# 01-PCIe.net
KiCad netlist of a schematic drawn in Altium Designer
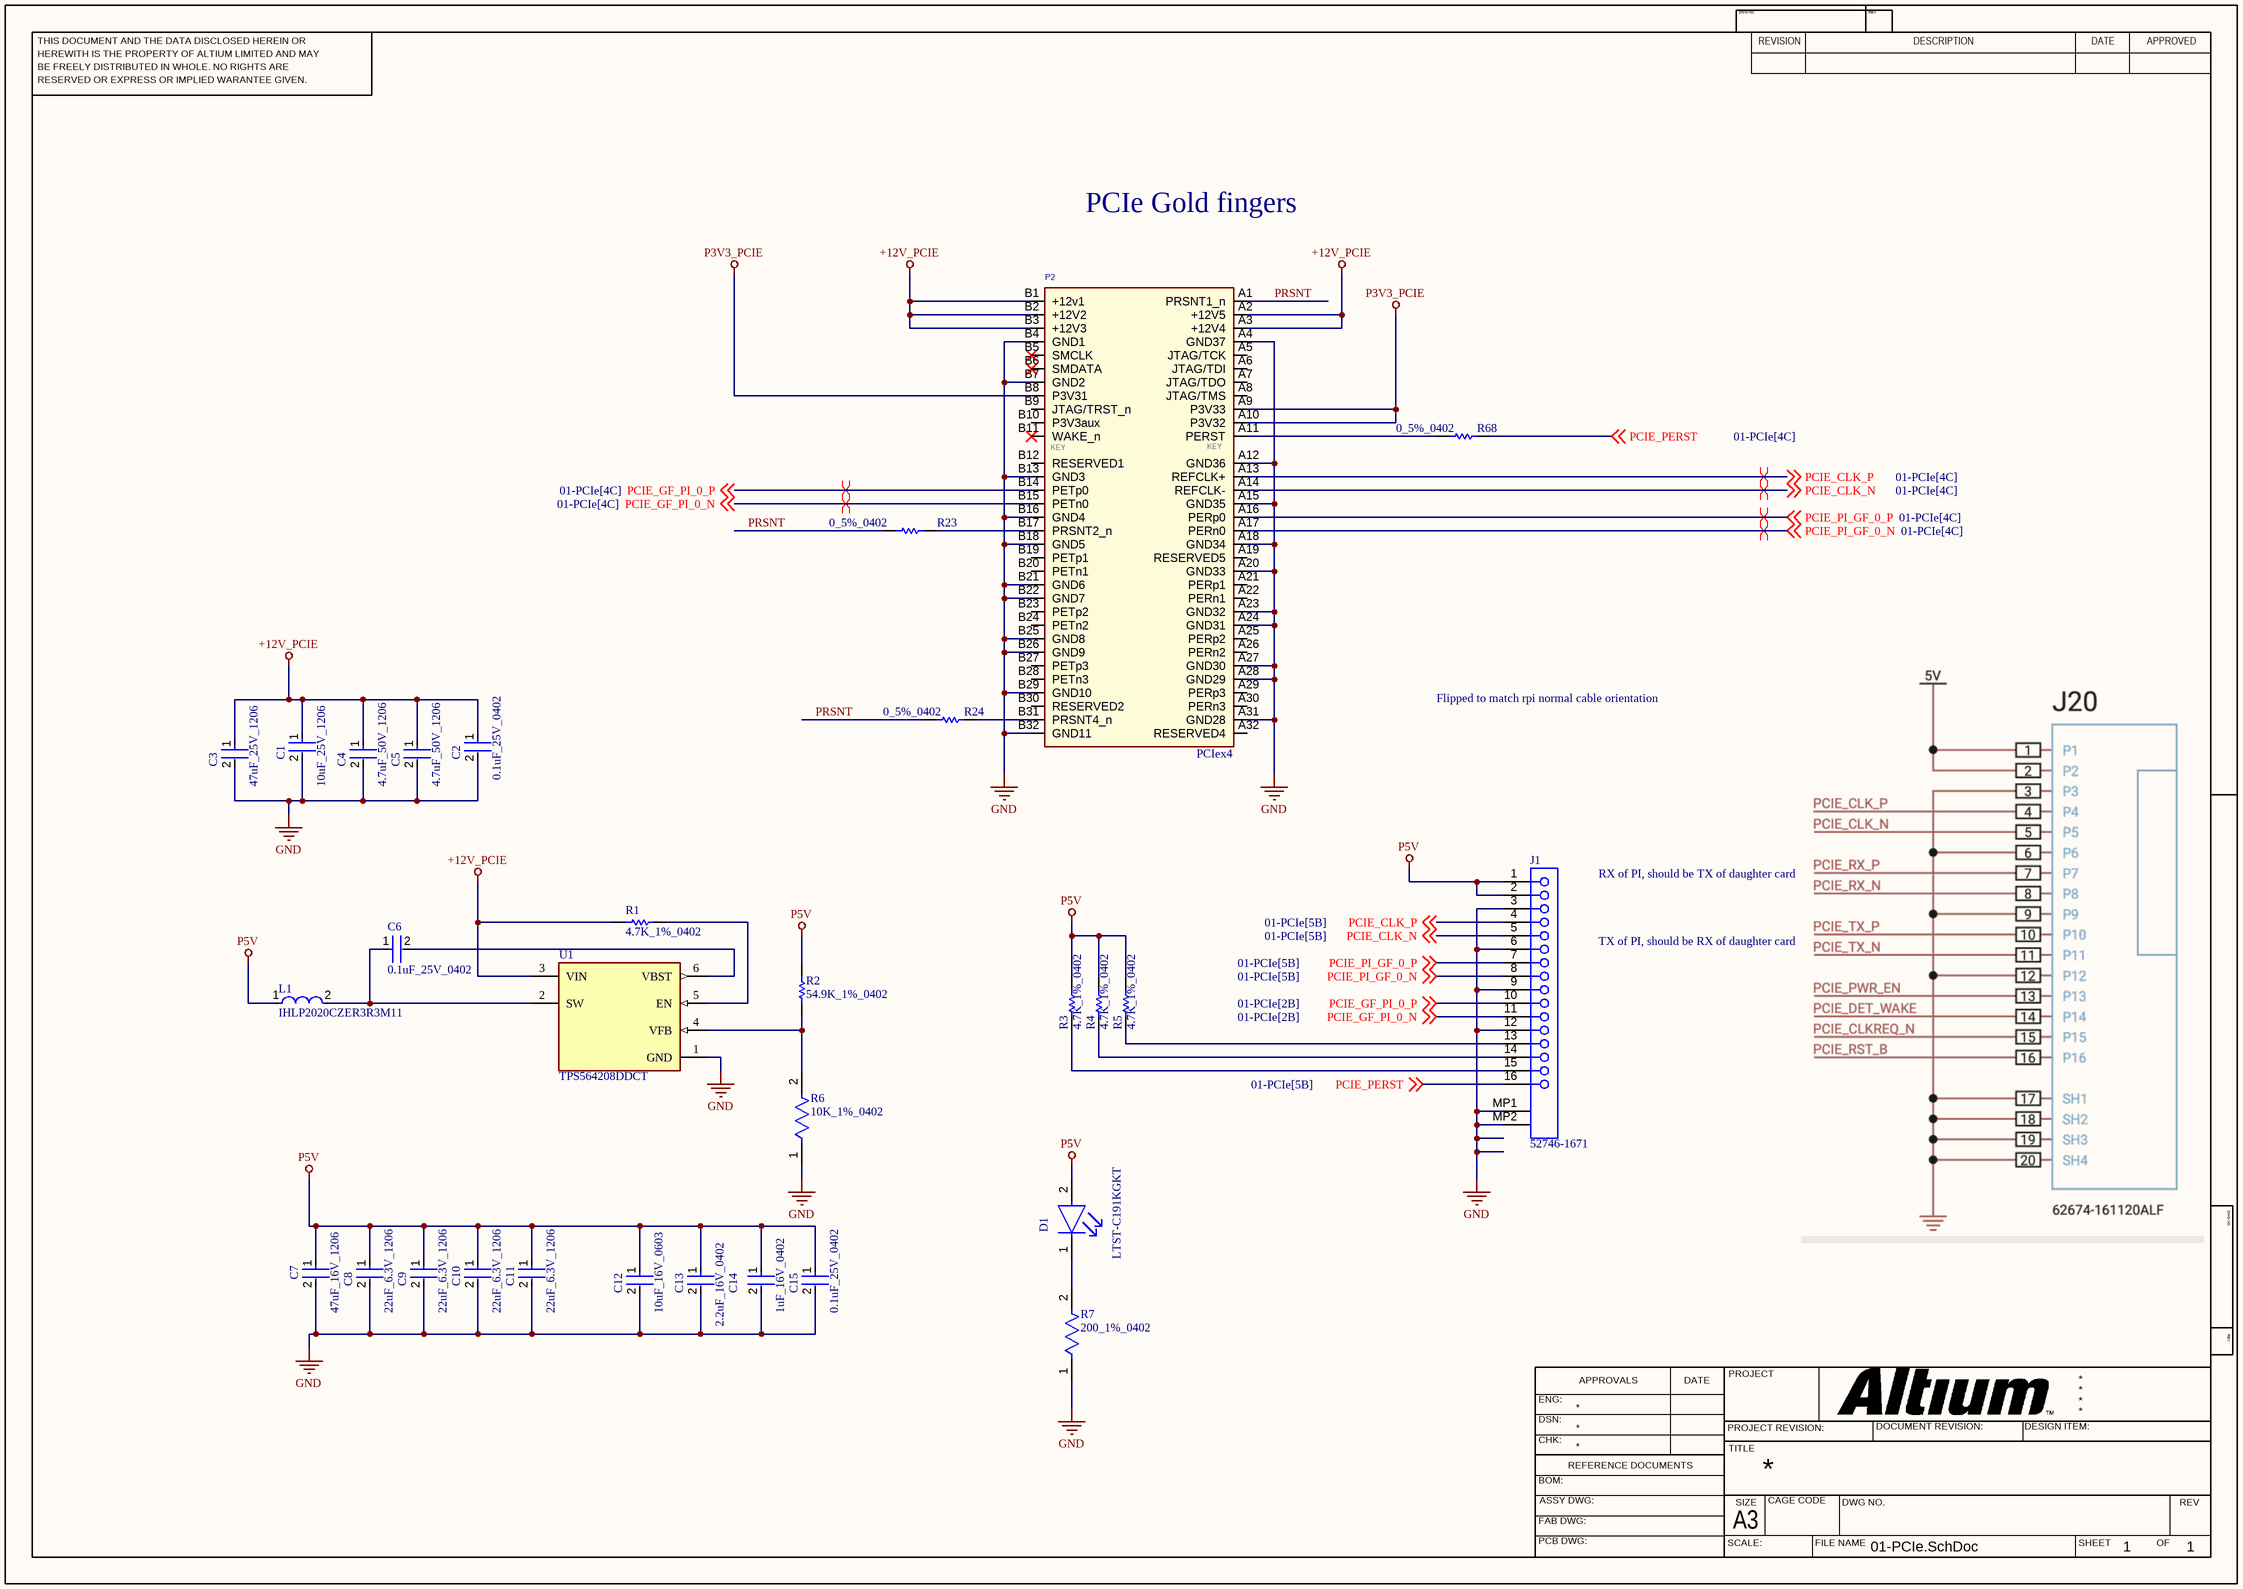
[diagram p0: 01-PCIe.SchDoc]

(export (version "E")
  (design (tool "Eeschema 10.0.6"))
  (components
    (comp (ref "C1")
      (value "10uF_25V_1206")
      (footprint "FP-1206-L_3_2_0_2-W_1_6_0-IPC_A")
      (description "General Purpose Ceramic Capacitor, 1206, 10uF, 20%, X5R, 15%, 25V")
      (fields (field (name "TOLERANCE") "20%"))
      (libsource (lib "Altium Content Vault") (part "02cd4be3c70576c341d710602a673aa"))
    )
    (comp (ref "C2")
      (value "0.1uF_25V_0402")
      (footprint "FP-0402-L_1_0_1-W_0_5_0_1-IPC_C")
      (description "General Purpose Ceramic Capacitor, 0402, 100nF, 10%, X7R, 15%, 25V")
      (fields (field (name "VOLTAGE") "25V") (field (name "TOLERANCE") "10%"))
      (libsource (lib "Altium Content Vault") (part "b4654b650e69147ec39a6b967a45e02"))
    )
    (comp (ref "C3")
      (value "47uF_25V_1206")
      (footprint "FP-C3216-160-0_2-MFG")
      (description "Multilayer Ceramic Capacitors 47uF ±20% 25V X5R SMD 1206")
      (fields (field (name "VOLTAGE") "25V") (field (name "TOLERANCE") "20%"))
      (libsource (lib "Altium Content Vault") (part "11868f565c42a9108669ba33697ecf6"))
    )
    (comp (ref "C4")
      (value "4.7uF_50V_1206")
      (footprint "FP-GRM31C-0_2-e0_3_0_8-IPC_C")
      (description "Chip Multilayer Ceramic Capacitors for General Purpose, 1206, 4.7uF, X7R, 15%, 10%, 50V")
      (fields (field (name "VOLTAGE") "50V") (field (name "TOLERANCE") "10%"))
      (libsource (lib "Altium Content Vault") (part "02cd4be3c70576c341d710602a673aa"))
    )
    (comp (ref "C5")
      (value "4.7uF_50V_1206")
      (footprint "FP-GRM31C-0_2-e0_3_0_8-IPC_C")
      (description "Chip Multilayer Ceramic Capacitors for General Purpose, 1206, 4.7uF, X7R, 15%, 10%, 50V")
      (fields (field (name "VOLTAGE") "50V") (field (name "TOLERANCE") "10%"))
      (libsource (lib "Altium Content Vault") (part "02cd4be3c70576c341d710602a673aa"))
    )
    (comp (ref "C6")
      (value "0.1uF_25V_0402")
      (footprint "FP-0402-L_1_0_1-W_0_5_0_1-IPC_C")
      (description "General Purpose Ceramic Capacitor, 0402, 100nF, 10%, X7R, 15%, 25V")
      (fields (field (name "VOLTAGE") "25V") (field (name "TOLERANCE") "10%"))
      (libsource (lib "Altium Content Vault") (part "b4654b650e69147ec39a6b967a45e02"))
    )
    (comp (ref "C7")
      (value "47uF_16V_1206")
      (footprint "FP-C3216-160-0_2-MFG")
      (description "Multilayer Ceramic Capacitors 47uF ±20% 16V X5R SMD 1206")
      (fields (field (name "TOLERANCE") "20%"))
      (libsource (lib "Altium Content Vault") (part "11868f565c42a9108669ba33697ecf6"))
    )
    (comp (ref "C8")
      (value "22uF_6.3V_1206")
      (footprint "FP-1206-L_3_2_0_2-W_1_6_0-IPC_C")
      (description "General Purpose Ceramic Capacitor, 1206, 22uF, 20%, X5R, 15%, 6.3V")
      (fields (field (name "TOLERANCE") "20%") (field (name "VOLTAGE") "6.3V"))
      (libsource (lib "Altium Content Vault") (part "02cd4be3c70576c341d710602a673aa"))
    )
    (comp (ref "C9")
      (value "22uF_6.3V_1206")
      (footprint "FP-1206-L_3_2_0_2-W_1_6_0-IPC_C")
      (description "General Purpose Ceramic Capacitor, 1206, 22uF, 20%, X5R, 15%, 6.3V")
      (fields (field (name "TOLERANCE") "20%") (field (name "VOLTAGE") "6.3V"))
      (libsource (lib "Altium Content Vault") (part "02cd4be3c70576c341d710602a673aa"))
    )
    (comp (ref "C10")
      (value "22uF_6.3V_1206")
      (footprint "FP-1206-L_3_2_0_2-W_1_6_0-IPC_C")
      (description "General Purpose Ceramic Capacitor, 1206, 22uF, 20%, X5R, 15%, 6.3V")
      (fields (field (name "TOLERANCE") "20%") (field (name "VOLTAGE") "6.3V"))
      (libsource (lib "Altium Content Vault") (part "02cd4be3c70576c341d710602a673aa"))
    )
    (comp (ref "C11")
      (value "22uF_6.3V_1206")
      (footprint "FP-1206-L_3_2_0_2-W_1_6_0-IPC_C")
      (description "General Purpose Ceramic Capacitor, 1206, 22uF, 20%, X5R, 15%, 6.3V")
      (fields (field (name "TOLERANCE") "20%") (field (name "VOLTAGE") "6.3V"))
      (libsource (lib "Altium Content Vault") (part "02cd4be3c70576c341d710602a673aa"))
    )
    (comp (ref "C12")
      (value "10uF_16V_0603")
      (footprint "FP-0603-L_1_6_0_2-W_0_8_0-MFG")
      (description "Multilayer Ceramic Capacitor 10uF 16V X5R 20% SMD 0603 T/R")
      (fields (field (name "TOLERANCE") "20%"))
      (libsource (lib "Altium Content Vault") (part "b4654b650e69147ec39a6b967a45e02"))
    )
    (comp (ref "C13")
      (value "2.2uF_16V_0402")
      (footprint "FP-C1005-050-0_05-IPC_A")
      (description "Multilayer Ceramic Capacitors 2.2μF ±10% 16V X5R SMD 0402")
      (fields (field (name "TOLERANCE") "10%"))
      (libsource (lib "Altium Content Vault") (part "b4654b650e69147ec39a6b967a45e02"))
    )
    (comp (ref "C14")
      (value "1uF_16V_0402")
      (footprint "FP-0402-L_1_0_0_05-W_0_5-IPC_A")
      (description "None")
      (fields (field (name "TOLERANCE") "10%"))
      (libsource (lib "Altium Content Vault") (part "b4654b650e69147ec39a6b967a45e02"))
    )
    (comp (ref "C15")
      (value "0.1uF_25V_0402")
      (footprint "FP-0402-L_1_0_1-W_0_5_0_1-IPC_C")
      (description "General Purpose Ceramic Capacitor, 0402, 100nF, 10%, X7R, 15%, 25V")
      (fields (field (name "VOLTAGE") "25V") (field (name "TOLERANCE") "10%"))
      (libsource (lib "Altium Content Vault") (part "b4654b650e69147ec39a6b967a45e02"))
    )
    (comp (ref "D1")
      (value "LTST-C191KGKT")
      (footprint "FP-LTST-C191KGKT-MFG")
      (description "LED GREEN CLEAR SMD")
      (libsource (lib "Altium Content Vault") (part "8706943c75ba83719d021d2fdc84c58"))
    )
    (comp (ref "J1")
      (value "52746-1671")
      (footprint "MOLX-52746-1671")
      (fields (field (name "MANUFACTURER") "Molex"))
      (libsource (lib "Altium Content Vault") (part "MOLX-52746-1671"))
    )
    (comp (ref "L1")
      (value "IHLP2020CZER3R3M11")
      (footprint "FP-IHLP-2020CZ-FP_1_905x2-MFG")
      (description "Fixed Inductors Commercial Low DCR Series 3.3uH 5.5A 40.4mΩ 20%")
      (fields (field (name "TOLERANCE") "20%"))
      (libsource (lib "Altium Content Vault") (part "725321dda6339637d4d059423bc1c3c"))
    )
    (comp (ref "P2")
      (value "PCIex4")
      (footprint "PCIE_4LANE_EDGE")
      (description "PCIE x4 Edge Connector,OrCAD Symbol,NC")
      (fields (field (name "PART NUMBER") "451") (field (name "MANUFACTURER") "NA"))
      (libsource (lib "Connectors") (part "PCIex4"))
    )
    (comp (ref "R1")
      (value "4.7K_1%_0402")
      (footprint "RESC1005X40X25NL10T10")
      (fields (field (name "MANUFACTURER") "Bourns") (field (name "PART NUMBER") "CR0402-FX-4701GLF"))
      (libsource (lib "Altium Content Vault") (part "RES"))
    )
    (comp (ref "R2")
      (value "54.9K_1%_0402")
      (footprint "RESC1005X40X25ML05T05")
      (fields (field (name "MANUFACTURER") "Panasonic") (field (name "PART NUMBER") "ERJ-2RKF5492X"))
      (libsource (lib "Altium Content Vault") (part "RES"))
    )
    (comp (ref "R3")
      (value "4.7K_1%_0402")
      (footprint "RESC1005X40X25NL10T10")
      (fields (field (name "MANUFACTURER") "Bourns") (field (name "PART NUMBER") "CR0402-FX-4701GLF"))
      (libsource (lib "Altium Content Vault") (part "RES"))
    )
    (comp (ref "R4")
      (value "4.7K_1%_0402")
      (footprint "RESC1005X40X25NL10T10")
      (fields (field (name "MANUFACTURER") "Bourns") (field (name "PART NUMBER") "CR0402-FX-4701GLF"))
      (libsource (lib "Altium Content Vault") (part "RES"))
    )
    (comp (ref "R5")
      (value "4.7K_1%_0402")
      (footprint "RESC1005X40X25NL10T10")
      (fields (field (name "MANUFACTURER") "Bourns") (field (name "PART NUMBER") "CR0402-FX-4701GLF"))
      (libsource (lib "Altium Content Vault") (part "RES"))
    )
    (comp (ref "R6")
      (value "10K_1%_0402")
      (footprint "FP-ERJU02-IPC_A")
      (description "RES 10K OHM 1% 1/10W 0402 SMD")
      (fields (field (name "TOLERANCE") "1%"))
      (libsource (lib "Altium Content Vault") (part "1029c3af85768c4190bb7ad29bc67b5"))
    )
    (comp (ref "R7")
      (value "200_1%_0402")
      (footprint "FP-ERJ2RK-IPC_A")
      (description "RES SMD 200 OHM 1% 1/10W 0402")
      (fields (field (name "TOLERANCE") "1%"))
      (libsource (lib "Altium Content Vault") (part "1029c3af85768c4190bb7ad29bc67b5"))
    )
    (comp (ref "R23")
      (value "0_5%_0402")
      (footprint "RESC1005X40X25LL10T10")
      (fields (field (name "MANUFACTURER") "KOA Speer") (field (name "PART NUMBER") "RK73Z1ETTP"))
      (libsource (lib "Altium Content Vault") (part "RES"))
    )
    (comp (ref "R24")
      (value "0_5%_0402")
      (footprint "RESC1005X40X25LL10T10")
      (fields (field (name "MANUFACTURER") "KOA Speer") (field (name "PART NUMBER") "RK73Z1ETTP"))
      (libsource (lib "Altium Content Vault") (part "RES"))
    )
    (comp (ref "R68")
      (value "0_5%_0402")
      (footprint "RESC1005X40X25LL10T10")
      (fields (field (name "MANUFACTURER") "KOA Speer") (field (name "PART NUMBER") "RK73Z1ETTP"))
      (libsource (lib "Altium Content Vault") (part "RES"))
    )
    (comp (ref "U1")
      (value "TPS564208DDCT")
      (footprint "FP-DDC0006A-IPC_C")
      (description "IC REG BUCK ADJ 4A TSOT23-6")
      (libsource (lib "Altium Content Vault") (part "38226ecfcda63a3f61967f0d2bdf495"))
    )
  )
  (nets
    (net (code "1") (name "+12V_PCIE") (class "Default")
      (node (ref "C1") (pin "1") (pinfunction "1_1") (pintype "passive"))
      (node (ref "C2") (pin "1") (pinfunction "1_1") (pintype "passive"))
      (node (ref "C3") (pin "1") (pinfunction "1_1") (pintype "passive"))
      (node (ref "C4") (pin "1") (pinfunction "1_1") (pintype "passive"))
      (node (ref "C5") (pin "1") (pinfunction "1_1") (pintype "passive"))
      (node (ref "P2") (pin "A2") (pinfunction "+12V5_A2") (pintype "passive"))
      (node (ref "P2") (pin "A3") (pinfunction "+12V4_A3") (pintype "passive"))
      (node (ref "P2") (pin "B1") (pinfunction "+12v1_B1") (pintype "power_in"))
      (node (ref "P2") (pin "B2") (pinfunction "+12V2_B2") (pintype "power_in"))
      (node (ref "P2") (pin "B3") (pinfunction "+12V3_B3") (pintype "power_in"))
      (node (ref "R1") (pin "2") (pinfunction "2_2") (pintype "passive"))
      (node (ref "U1") (pin "3") (pinfunction "VIN_3") (pintype "power_in"))
    )
    (net (code "2") (name "/PRSNT") (class "Default")
      (node (ref "P2") (pin "A1") (pinfunction "PRSNT1_n_A1") (pintype "passive"))
      (node (ref "R23") (pin "1") (pinfunction "1_1") (pintype "passive"))
      (node (ref "R24") (pin "1") (pinfunction "1_1") (pintype "passive"))
    )
    (net (code "3") (name "GND") (class "Default")
      (node (ref "C1") (pin "2") (pinfunction "2_2") (pintype "passive"))
      (node (ref "C10") (pin "2") (pinfunction "2_2") (pintype "passive"))
      (node (ref "C11") (pin "2") (pinfunction "2_2") (pintype "passive"))
      (node (ref "C12") (pin "2") (pinfunction "2_2") (pintype "passive"))
      (node (ref "C13") (pin "2") (pinfunction "2_2") (pintype "passive"))
      (node (ref "C14") (pin "2") (pinfunction "2_2") (pintype "passive"))
      (node (ref "C15") (pin "2") (pinfunction "2_2") (pintype "passive"))
      (node (ref "C2") (pin "2") (pinfunction "2_2") (pintype "passive"))
      (node (ref "C3") (pin "2") (pinfunction "2_2") (pintype "passive"))
      (node (ref "C4") (pin "2") (pinfunction "2_2") (pintype "passive"))
      (node (ref "C5") (pin "2") (pinfunction "2_2") (pintype "passive"))
      (node (ref "C7") (pin "2") (pinfunction "2_2") (pintype "passive"))
      (node (ref "C8") (pin "2") (pinfunction "2_2") (pintype "passive"))
      (node (ref "C9") (pin "2") (pinfunction "2_2") (pintype "passive"))
      (node (ref "J1") (pin "12") (pinfunction "12_12") (pintype "passive"))
      (node (ref "J1") (pin "3") (pinfunction "3_3") (pintype "passive"))
      (node (ref "J1") (pin "6") (pinfunction "6_6") (pintype "passive"))
      (node (ref "J1") (pin "9") (pinfunction "9_9") (pintype "passive"))
      (node (ref "J1") (pin "MP1") (pinfunction "MP1_MP1") (pintype "passive"))
      (node (ref "J1") (pin "MP2") (pinfunction "MP2_MP2") (pintype "passive"))
      (node (ref "P2") (pin "A12") (pinfunction "GND36_A12") (pintype "power_in"))
      (node (ref "P2") (pin "A15") (pinfunction "GND35_A15") (pintype "power_in"))
      (node (ref "P2") (pin "A18") (pinfunction "GND34_A18") (pintype "power_in"))
      (node (ref "P2") (pin "A20") (pinfunction "GND33_A20") (pintype "power_in"))
      (node (ref "P2") (pin "A23") (pinfunction "GND32_A23") (pintype "power_in"))
      (node (ref "P2") (pin "A24") (pinfunction "GND31_A24") (pintype "power_in"))
      (node (ref "P2") (pin "A27") (pinfunction "GND30_A27") (pintype "power_in"))
      (node (ref "P2") (pin "A28") (pinfunction "GND29_A28") (pintype "power_in"))
      (node (ref "P2") (pin "A31") (pinfunction "GND28_A31") (pintype "power_in"))
      (node (ref "P2") (pin "A4") (pinfunction "GND37_A4") (pintype "power_in"))
      (node (ref "P2") (pin "B13") (pinfunction "GND3_B13") (pintype "power_in"))
      (node (ref "P2") (pin "B16") (pinfunction "GND4_B16") (pintype "power_in"))
      (node (ref "P2") (pin "B18") (pinfunction "GND5_B18") (pintype "power_in"))
      (node (ref "P2") (pin "B21") (pinfunction "GND6_B21") (pintype "power_in"))
      (node (ref "P2") (pin "B22") (pinfunction "GND7_B22") (pintype "power_in"))
      (node (ref "P2") (pin "B25") (pinfunction "GND8_B25") (pintype "power_in"))
      (node (ref "P2") (pin "B26") (pinfunction "GND9_B26") (pintype "power_in"))
      (node (ref "P2") (pin "B29") (pinfunction "GND10_B29") (pintype "power_in"))
      (node (ref "P2") (pin "B32") (pinfunction "GND11_B32") (pintype "power_in"))
      (node (ref "P2") (pin "B4") (pinfunction "GND1_B4") (pintype "power_in"))
      (node (ref "P2") (pin "B7") (pinfunction "GND2_B7") (pintype "power_in"))
      (node (ref "R6") (pin "1") (pinfunction "1_1") (pintype "passive"))
      (node (ref "R7") (pin "1") (pinfunction "1_1") (pintype "passive"))
      (node (ref "U1") (pin "1") (pinfunction "GND_1") (pintype "power_in"))
    )
    (net (code "4") (name "Net-(D1-C)") (class "Default")
      (node (ref "D1") (pin "1") (pinfunction "C_1") (pintype "passive"))
      (node (ref "R7") (pin "2") (pinfunction "2_2") (pintype "passive"))
    )
    (net (code "5") (name "Net-(J1-Pad13)") (class "Default")
      (node (ref "J1") (pin "13") (pinfunction "13_13") (pintype "passive"))
      (node (ref "R5") (pin "1") (pinfunction "1_1") (pintype "passive"))
    )
    (net (code "6") (name "Net-(J1-Pad14)") (class "Default")
      (node (ref "J1") (pin "14") (pinfunction "14_14") (pintype "passive"))
      (node (ref "R4") (pin "1") (pinfunction "1_1") (pintype "passive"))
    )
    (net (code "7") (name "Net-(J1-Pad15)") (class "Default")
      (node (ref "J1") (pin "15") (pinfunction "15_15") (pintype "passive"))
      (node (ref "R3") (pin "1") (pinfunction "1_1") (pintype "passive"))
    )
    (net (code "8") (name "Net-(P2-PERST)") (class "Default")
      (node (ref "P2") (pin "A11") (pinfunction "PERST_A11") (pintype "passive"))
      (node (ref "R68") (pin "1") (pinfunction "1_1") (pintype "passive"))
    )
    (net (code "9") (name "Net-(P2-PRSNT2_n)") (class "Default")
      (node (ref "P2") (pin "B17") (pinfunction "PRSNT2_n_B17") (pintype "passive"))
      (node (ref "R23") (pin "2") (pinfunction "2_2") (pintype "passive"))
    )
    (net (code "10") (name "Net-(P2-PRSNT4_n)") (class "Default")
      (node (ref "P2") (pin "B31") (pinfunction "PRSNT4_n_B31") (pintype "passive"))
      (node (ref "R24") (pin "2") (pinfunction "2_2") (pintype "passive"))
    )
    (net (code "11") (name "Net-(U1-EN)") (class "Default")
      (node (ref "R1") (pin "1") (pinfunction "1_1") (pintype "passive"))
      (node (ref "U1") (pin "5") (pinfunction "EN_5") (pintype "input"))
    )
    (net (code "12") (name "Net-(U1-SW)") (class "Default")
      (node (ref "C6") (pin "1") (pinfunction "1_1") (pintype "passive"))
      (node (ref "L1") (pin "2") (pinfunction "2_2") (pintype "passive"))
      (node (ref "U1") (pin "2") (pinfunction "SW_2") (pintype "passive"))
    )
    (net (code "13") (name "Net-(U1-VBST)") (class "Default")
      (node (ref "C6") (pin "2") (pinfunction "2_2") (pintype "passive"))
      (node (ref "U1") (pin "6") (pinfunction "VBST_6") (pintype "output"))
    )
    (net (code "14") (name "Net-(U1-VFB)") (class "Default")
      (node (ref "R2") (pin "1") (pinfunction "1_1") (pintype "passive"))
      (node (ref "R6") (pin "2") (pinfunction "2_2") (pintype "passive"))
      (node (ref "U1") (pin "4") (pinfunction "VFB_4") (pintype "input"))
    )
    (net (code "15") (name "P3V3_PCIE") (class "Default")
      (node (ref "P2") (pin "A10") (pinfunction "P3V32_A10") (pintype "passive"))
      (node (ref "P2") (pin "A9") (pinfunction "P3V33_A9") (pintype "passive"))
      (node (ref "P2") (pin "B8") (pinfunction "P3V31_B8") (pintype "power_in"))
    )
    (net (code "16") (name "P5V") (class "Default")
      (node (ref "C10") (pin "1") (pinfunction "1_1") (pintype "passive"))
      (node (ref "C11") (pin "1") (pinfunction "1_1") (pintype "passive"))
      (node (ref "C12") (pin "1") (pinfunction "1_1") (pintype "passive"))
      (node (ref "C13") (pin "1") (pinfunction "1_1") (pintype "passive"))
      (node (ref "C14") (pin "1") (pinfunction "1_1") (pintype "passive"))
      (node (ref "C15") (pin "1") (pinfunction "1_1") (pintype "passive"))
      (node (ref "C7") (pin "1") (pinfunction "1_1") (pintype "passive"))
      (node (ref "C8") (pin "1") (pinfunction "1_1") (pintype "passive"))
      (node (ref "C9") (pin "1") (pinfunction "1_1") (pintype "passive"))
      (node (ref "D1") (pin "2") (pinfunction "A_2") (pintype "passive"))
      (node (ref "J1") (pin "1") (pinfunction "1_1") (pintype "passive"))
      (node (ref "J1") (pin "2") (pinfunction "2_2") (pintype "passive"))
      (node (ref "L1") (pin "1") (pinfunction "1_1") (pintype "passive"))
      (node (ref "R2") (pin "2") (pinfunction "2_2") (pintype "passive"))
      (node (ref "R3") (pin "2") (pinfunction "2_2") (pintype "passive"))
      (node (ref "R4") (pin "2") (pinfunction "2_2") (pintype "passive"))
      (node (ref "R5") (pin "2") (pinfunction "2_2") (pintype "passive"))
    )
    (net (code "17") (name "PCIE_CLK_N") (class "Default")
      (node (ref "J1") (pin "5") (pinfunction "5_5") (pintype "passive"))
      (node (ref "P2") (pin "A14") (pinfunction "REFCLK-_A14") (pintype "passive"))
    )
    (net (code "18") (name "PCIE_CLK_P") (class "Default")
      (node (ref "J1") (pin "4") (pinfunction "4_4") (pintype "passive"))
      (node (ref "P2") (pin "A13") (pinfunction "REFCLK+_A13") (pintype "passive"))
    )
    (net (code "19") (name "PCIE_GF_PI_0_N") (class "Default")
      (node (ref "J1") (pin "11") (pinfunction "11_11") (pintype "passive"))
      (node (ref "P2") (pin "B15") (pinfunction "PETn0_B15") (pintype "passive"))
    )
    (net (code "20") (name "PCIE_GF_PI_0_P") (class "Default")
      (node (ref "J1") (pin "10") (pinfunction "10_10") (pintype "passive"))
      (node (ref "P2") (pin "B14") (pinfunction "PETp0_B14") (pintype "passive"))
    )
    (net (code "21") (name "PCIE_PERST") (class "Default")
      (node (ref "J1") (pin "16") (pinfunction "16_16") (pintype "passive"))
      (node (ref "R68") (pin "2") (pinfunction "2_2") (pintype "passive"))
    )
    (net (code "22") (name "PCIE_PI_GF_0_N") (class "Default")
      (node (ref "J1") (pin "8") (pinfunction "8_8") (pintype "passive"))
      (node (ref "P2") (pin "A17") (pinfunction "PERn0_A17") (pintype "passive"))
    )
    (net (code "23") (name "PCIE_PI_GF_0_P") (class "Default")
      (node (ref "J1") (pin "7") (pinfunction "7_7") (pintype "passive"))
      (node (ref "P2") (pin "A16") (pinfunction "PERp0_A16") (pintype "passive"))
    )
    (net (code "24") (name "unconnected-(P2-JTAG{slash}TCK-PadA5)") (class "Default")
      (node (ref "P2") (pin "A5") (pinfunction "JTAG/TCK_A5") (pintype "passive"))
    )
    (net (code "25") (name "unconnected-(P2-JTAG{slash}TDI-PadA6)") (class "Default")
      (node (ref "P2") (pin "A6") (pinfunction "JTAG/TDI_A6") (pintype "passive"))
    )
    (net (code "26") (name "unconnected-(P2-JTAG{slash}TDO-PadA7)") (class "Default")
      (node (ref "P2") (pin "A7") (pinfunction "JTAG/TDO_A7") (pintype "passive"))
    )
    (net (code "27") (name "unconnected-(P2-JTAG{slash}TMS-PadA8)") (class "Default")
      (node (ref "P2") (pin "A8") (pinfunction "JTAG/TMS_A8") (pintype "passive"))
    )
    (net (code "28") (name "unconnected-(P2-JTAG{slash}TRST_n-PadB9)") (class "Default")
      (node (ref "P2") (pin "B9") (pinfunction "JTAG/TRST_n_B9") (pintype "passive"))
    )
    (net (code "29") (name "unconnected-(P2-P3V3aux-PadB10)") (class "Default")
      (node (ref "P2") (pin "B10") (pinfunction "P3V3aux_B10") (pintype "passive"))
    )
    (net (code "30") (name "unconnected-(P2-PERn1-PadA22)") (class "Default")
      (node (ref "P2") (pin "A22") (pinfunction "PERn1_A22") (pintype "passive"))
    )
    (net (code "31") (name "unconnected-(P2-PERn2-PadA26)") (class "Default")
      (node (ref "P2") (pin "A26") (pinfunction "PERn2_A26") (pintype "passive"))
    )
    (net (code "32") (name "unconnected-(P2-PERn3-PadA30)") (class "Default")
      (node (ref "P2") (pin "A30") (pinfunction "PERn3_A30") (pintype "passive"))
    )
    (net (code "33") (name "unconnected-(P2-PERp1-PadA21)") (class "Default")
      (node (ref "P2") (pin "A21") (pinfunction "PERp1_A21") (pintype "passive"))
    )
    (net (code "34") (name "unconnected-(P2-PERp2-PadA25)") (class "Default")
      (node (ref "P2") (pin "A25") (pinfunction "PERp2_A25") (pintype "passive"))
    )
    (net (code "35") (name "unconnected-(P2-PERp3-PadA29)") (class "Default")
      (node (ref "P2") (pin "A29") (pinfunction "PERp3_A29") (pintype "passive"))
    )
    (net (code "36") (name "unconnected-(P2-PETn1-PadB20)") (class "Default")
      (node (ref "P2") (pin "B20") (pinfunction "PETn1_B20") (pintype "passive"))
    )
    (net (code "37") (name "unconnected-(P2-PETn2-PadB24)") (class "Default")
      (node (ref "P2") (pin "B24") (pinfunction "PETn2_B24") (pintype "passive"))
    )
    (net (code "38") (name "unconnected-(P2-PETn3-PadB28)") (class "Default")
      (node (ref "P2") (pin "B28") (pinfunction "PETn3_B28") (pintype "passive"))
    )
    (net (code "39") (name "unconnected-(P2-PETp1-PadB19)") (class "Default")
      (node (ref "P2") (pin "B19") (pinfunction "PETp1_B19") (pintype "passive"))
    )
    (net (code "40") (name "unconnected-(P2-PETp2-PadB23)") (class "Default")
      (node (ref "P2") (pin "B23") (pinfunction "PETp2_B23") (pintype "passive"))
    )
    (net (code "41") (name "unconnected-(P2-PETp3-PadB27)") (class "Default")
      (node (ref "P2") (pin "B27") (pinfunction "PETp3_B27") (pintype "passive"))
    )
    (net (code "42") (name "unconnected-(P2-RESERVED1-PadB12)") (class "Default")
      (node (ref "P2") (pin "B12") (pinfunction "RESERVED1_B12") (pintype "passive"))
    )
    (net (code "43") (name "unconnected-(P2-RESERVED2-PadB30)") (class "Default")
      (node (ref "P2") (pin "B30") (pinfunction "RESERVED2_B30") (pintype "passive"))
    )
    (net (code "44") (name "unconnected-(P2-RESERVED4-PadA32)") (class "Default")
      (node (ref "P2") (pin "A32") (pinfunction "RESERVED4_A32") (pintype "passive"))
    )
    (net (code "45") (name "unconnected-(P2-RESERVED5-PadA19)") (class "Default")
      (node (ref "P2") (pin "A19") (pinfunction "RESERVED5_A19") (pintype "passive"))
    )
    (net (code "46") (name "unconnected-(P2-SMCLK-PadB5)") (class "Default")
      (node (ref "P2") (pin "B5") (pinfunction "SMCLK_B5") (pintype "passive+no_connect"))
    )
    (net (code "47") (name "unconnected-(P2-SMDATA-PadB6)") (class "Default")
      (node (ref "P2") (pin "B6") (pinfunction "SMDATA_B6") (pintype "passive+no_connect"))
    )
    (net (code "48") (name "unconnected-(P2-WAKE_n-PadB11)") (class "Default")
      (node (ref "P2") (pin "B11") (pinfunction "WAKE_n_B11") (pintype "passive+no_connect"))
    )
  )
)
